# oLoRa-part-thi.net
KiCad netlist of a schematic drawn in EasyEDA
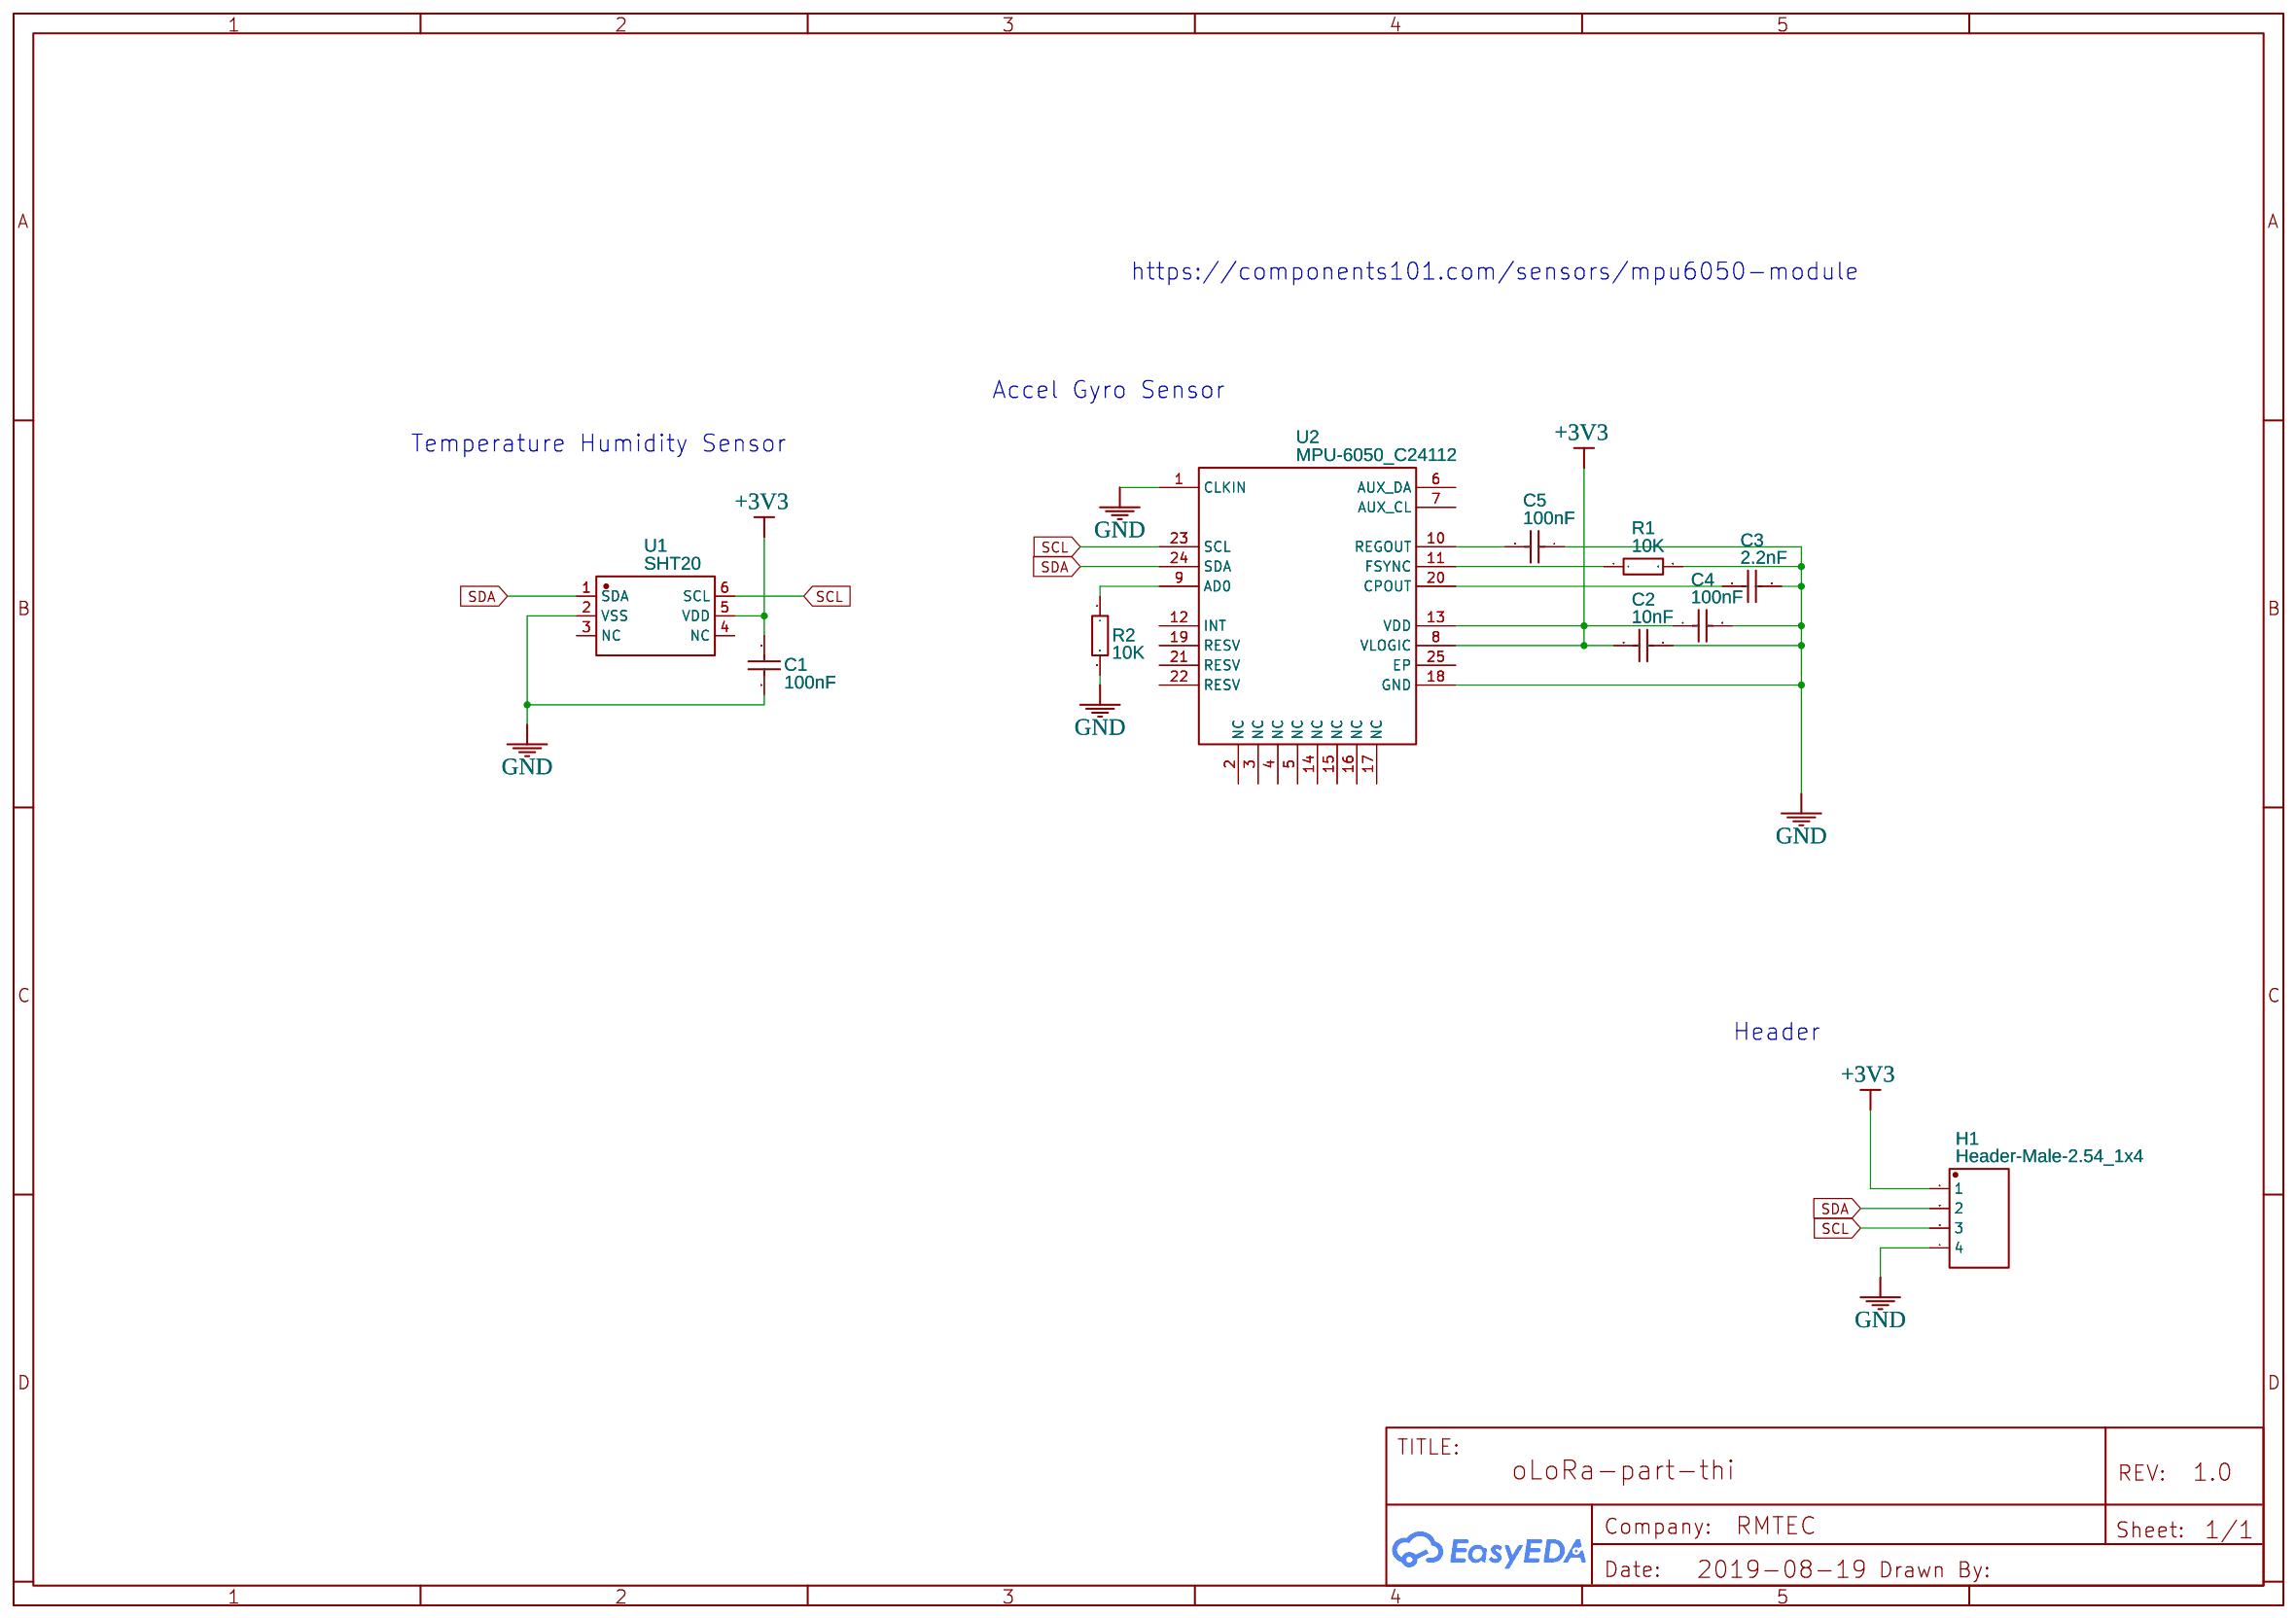
[diagram p0: schematic sheet]

(export (version "E")
  (design (tool "Eeschema 10.0.6"))
  (components
    (comp (ref "C1")
      (value "100nF")
      (fields
        (field (name "BOM_Manufacturer Part") "0603B104K500NT")
        (field (name "BOM_Supplier Part") "C30926")
      )
      (libsource (lib "") (part "0603B104K500NT_1"))
    )
    (comp (ref "C2")
      (value "10nF")
      (fields
        (field (name "BOM_Manufacturer Part") "CC0603KRX7R9BB103")
        (field (name "BOM_Supplier Part") "C100042")
      )
      (libsource (lib "") (part "CC0603KRX7R9BB103"))
    )
    (comp (ref "C3")
      (value "2.2nF")
      (fields
        (field (name "BOM_Manufacturer Part") "CC0603KRX7R9BB222")
        (field (name "BOM_Supplier Part") "C107082")
      )
      (libsource (lib "") (part "CC0603KRX7R9BB222"))
    )
    (comp (ref "C4")
      (value "100nF")
      (fields
        (field (name "BOM_Manufacturer Part") "0603B104K500NT")
        (field (name "BOM_Supplier Part") "C30926")
      )
      (libsource (lib "") (part "0603B104K500NT_2"))
    )
    (comp (ref "C5")
      (value "100nF")
      (fields
        (field (name "BOM_Manufacturer Part") "0603B104K500NT")
        (field (name "BOM_Supplier Part") "C30926")
      )
      (libsource (lib "") (part "0603B104K500NT"))
    )
    (comp (ref "H1")
      (value "Header-Male-2.54_1x4")
      (fields
        (field (name "BOM_Manufacturer Part") "210S-1*4P L=11.6MMGold-plated black")
        (field (name "BOM_Supplier Part") "C124378")
      )
      (libsource (lib "") (part "Unknown_990_610"))
    )
    (comp (ref "R1")
      (value "10K")
      (fields
        (field (name "BOM_Manufacturer Part") "RC0603FR-0710KL")
        (field (name "BOM_Supplier Part") "C98220")
      )
      (libsource (lib "") (part "RC0603FR-0710KL_1"))
    )
    (comp (ref "R2")
      (value "10K")
      (fields
        (field (name "BOM_Manufacturer Part") "RC0603FR-0710KL")
        (field (name "BOM_Supplier Part") "C98220")
      )
      (libsource (lib "") (part "RC0603FR-0710KL"))
    )
    (comp (ref "U1")
      (value "SHT20")
      (fields (field (name "BOM_Supplier Part") "C53865"))
      (libsource (lib "") (part "Unknown_325_305"))
    )
    (comp (ref "U2")
      (value "MPU-6050_C24112")
      (fields (field (name "BOM_Manufacturer Part") "MPU-6050") (field (name "BOM_Supplier Part") "C24112"))
      (libsource (lib "") (part "Unknown_660_310"))
    )
  )
  (nets
    (net (code "1") (name "+3V3") (class "Default")
      (node (ref "C1") (pin "1") (pinfunction "1_1") (pintype "input"))
      (node (ref "C2") (pin "2") (pinfunction "2_2") (pintype "input"))
      (node (ref "C4") (pin "1") (pinfunction "1_1") (pintype "input"))
      (node (ref "H1") (pin "1") (pinfunction "1_1") (pintype "unspecified"))
      (node (ref "U1") (pin "5") (pinfunction "VDD_5") (pintype "unspecified"))
      (node (ref "U2") (pin "13") (pinfunction "VDD_13") (pintype "passive"))
      (node (ref "U2") (pin "8") (pinfunction "VLOGIC_8") (pintype "passive"))
    )
    (net (code "2") (name "GND") (class "Default")
      (node (ref "C1") (pin "2") (pinfunction "2_2") (pintype "input"))
      (node (ref "C2") (pin "1") (pinfunction "1_1") (pintype "input"))
      (node (ref "C3") (pin "1") (pinfunction "1_1") (pintype "input"))
      (node (ref "C4") (pin "2") (pinfunction "2_2") (pintype "input"))
      (node (ref "C5") (pin "1") (pinfunction "1_1") (pintype "input"))
      (node (ref "H1") (pin "4") (pinfunction "4_4") (pintype "unspecified"))
      (node (ref "R1") (pin "2") (pinfunction "2_2") (pintype "input"))
      (node (ref "R2") (pin "2") (pinfunction "2_2") (pintype "input"))
      (node (ref "U1") (pin "2") (pinfunction "VSS_2") (pintype "unspecified"))
      (node (ref "U2") (pin "1") (pinfunction "CLKIN_1") (pintype "input"))
      (node (ref "U2") (pin "18") (pinfunction "GND_18") (pintype "passive"))
    )
    (net (code "3") (name "Net-(U2-AD0)") (class "Default")
      (node (ref "R2") (pin "1") (pinfunction "1_1") (pintype "input"))
      (node (ref "U2") (pin "9") (pinfunction "AD0_9") (pintype "input"))
    )
    (net (code "4") (name "Net-(U2-CPOUT)") (class "Default")
      (node (ref "C3") (pin "2") (pinfunction "2_2") (pintype "input"))
      (node (ref "U2") (pin "20") (pinfunction "CPOUT_20") (pintype "output"))
    )
    (net (code "5") (name "Net-(U2-FSYNC)") (class "Default")
      (node (ref "R1") (pin "1") (pinfunction "1_1") (pintype "input"))
      (node (ref "U2") (pin "11") (pinfunction "FSYNC_11") (pintype "input"))
    )
    (net (code "6") (name "Net-(U2-REGOUT)") (class "Default")
      (node (ref "C5") (pin "2") (pinfunction "2_2") (pintype "input"))
      (node (ref "U2") (pin "10") (pinfunction "REGOUT_10") (pintype "output"))
    )
    (net (code "7") (name "SCL") (class "Default")
      (node (ref "H1") (pin "3") (pinfunction "3_3") (pintype "unspecified"))
      (node (ref "U1") (pin "6") (pinfunction "SCL_6") (pintype "unspecified"))
      (node (ref "U2") (pin "23") (pinfunction "SCL_23") (pintype "input"))
    )
    (net (code "8") (name "SDA") (class "Default")
      (node (ref "H1") (pin "2") (pinfunction "2_2") (pintype "unspecified"))
      (node (ref "U1") (pin "1") (pinfunction "SDA_1") (pintype "unspecified"))
      (node (ref "U2") (pin "24") (pinfunction "SDA_24") (pintype "unspecified"))
    )
    (net (code "9") (name "unconnected-(U1-NC-Pad3)") (class "Default")
      (node (ref "U1") (pin "3") (pinfunction "NC_3") (pintype "unspecified"))
    )
    (net (code "10") (name "unconnected-(U1-NC-Pad4)") (class "Default")
      (node (ref "U1") (pin "4") (pinfunction "NC_4") (pintype "unspecified"))
    )
    (net (code "11") (name "unconnected-(U2-AUX_CL-Pad7)") (class "Default")
      (node (ref "U2") (pin "7") (pinfunction "AUX_CL_7") (pintype "unspecified"))
    )
    (net (code "12") (name "unconnected-(U2-AUX_DA-Pad6)") (class "Default")
      (node (ref "U2") (pin "6") (pinfunction "AUX_DA_6") (pintype "unspecified"))
    )
    (net (code "13") (name "unconnected-(U2-EP-Pad25)") (class "Default")
      (node (ref "U2") (pin "25") (pinfunction "EP_25") (pintype "passive"))
    )
    (net (code "14") (name "unconnected-(U2-INT-Pad12)") (class "Default")
      (node (ref "U2") (pin "12") (pinfunction "INT_12") (pintype "unspecified"))
    )
    (net (code "15") (name "unconnected-(U2-NC-Pad2)") (class "Default")
      (node (ref "U2") (pin "2") (pinfunction "NC_2") (pintype "unspecified"))
    )
    (net (code "16") (name "unconnected-(U2-NC-Pad3)") (class "Default")
      (node (ref "U2") (pin "3") (pinfunction "NC_3") (pintype "unspecified"))
    )
    (net (code "17") (name "unconnected-(U2-NC-Pad4)") (class "Default")
      (node (ref "U2") (pin "4") (pinfunction "NC_4") (pintype "unspecified"))
    )
    (net (code "18") (name "unconnected-(U2-NC-Pad5)") (class "Default")
      (node (ref "U2") (pin "5") (pinfunction "NC_5") (pintype "unspecified"))
    )
    (net (code "19") (name "unconnected-(U2-NC-Pad14)") (class "Default")
      (node (ref "U2") (pin "14") (pinfunction "NC_14") (pintype "unspecified"))
    )
    (net (code "20") (name "unconnected-(U2-NC-Pad15)") (class "Default")
      (node (ref "U2") (pin "15") (pinfunction "NC_15") (pintype "unspecified"))
    )
    (net (code "21") (name "unconnected-(U2-NC-Pad16)") (class "Default")
      (node (ref "U2") (pin "16") (pinfunction "NC_16") (pintype "unspecified"))
    )
    (net (code "22") (name "unconnected-(U2-NC-Pad17)") (class "Default")
      (node (ref "U2") (pin "17") (pinfunction "NC_17") (pintype "unspecified"))
    )
    (net (code "23") (name "unconnected-(U2-RESV-Pad19)") (class "Default")
      (node (ref "U2") (pin "19") (pinfunction "RESV_19") (pintype "unspecified"))
    )
    (net (code "24") (name "unconnected-(U2-RESV-Pad21)") (class "Default")
      (node (ref "U2") (pin "21") (pinfunction "RESV_21") (pintype "unspecified"))
    )
    (net (code "25") (name "unconnected-(U2-RESV-Pad22)") (class "Default")
      (node (ref "U2") (pin "22") (pinfunction "RESV_22") (pintype "unspecified"))
    )
  )
)
